# ground_station_DTMF.net
KiCad netlist of a schematic drawn in Altium Designer
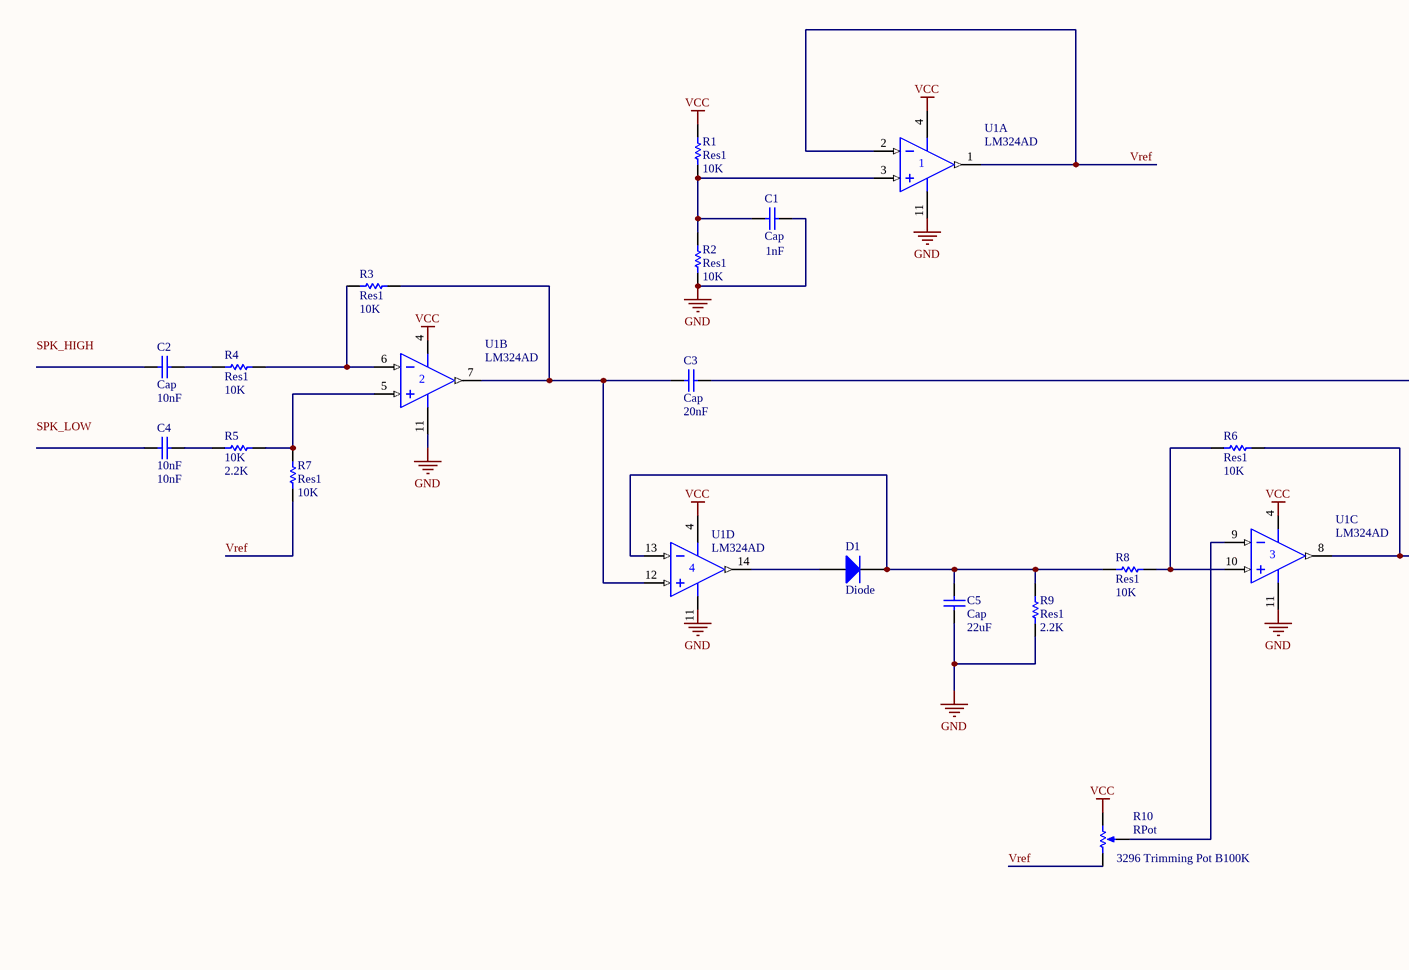
[diagram p0: ground station DTMF.SchDoc, left]
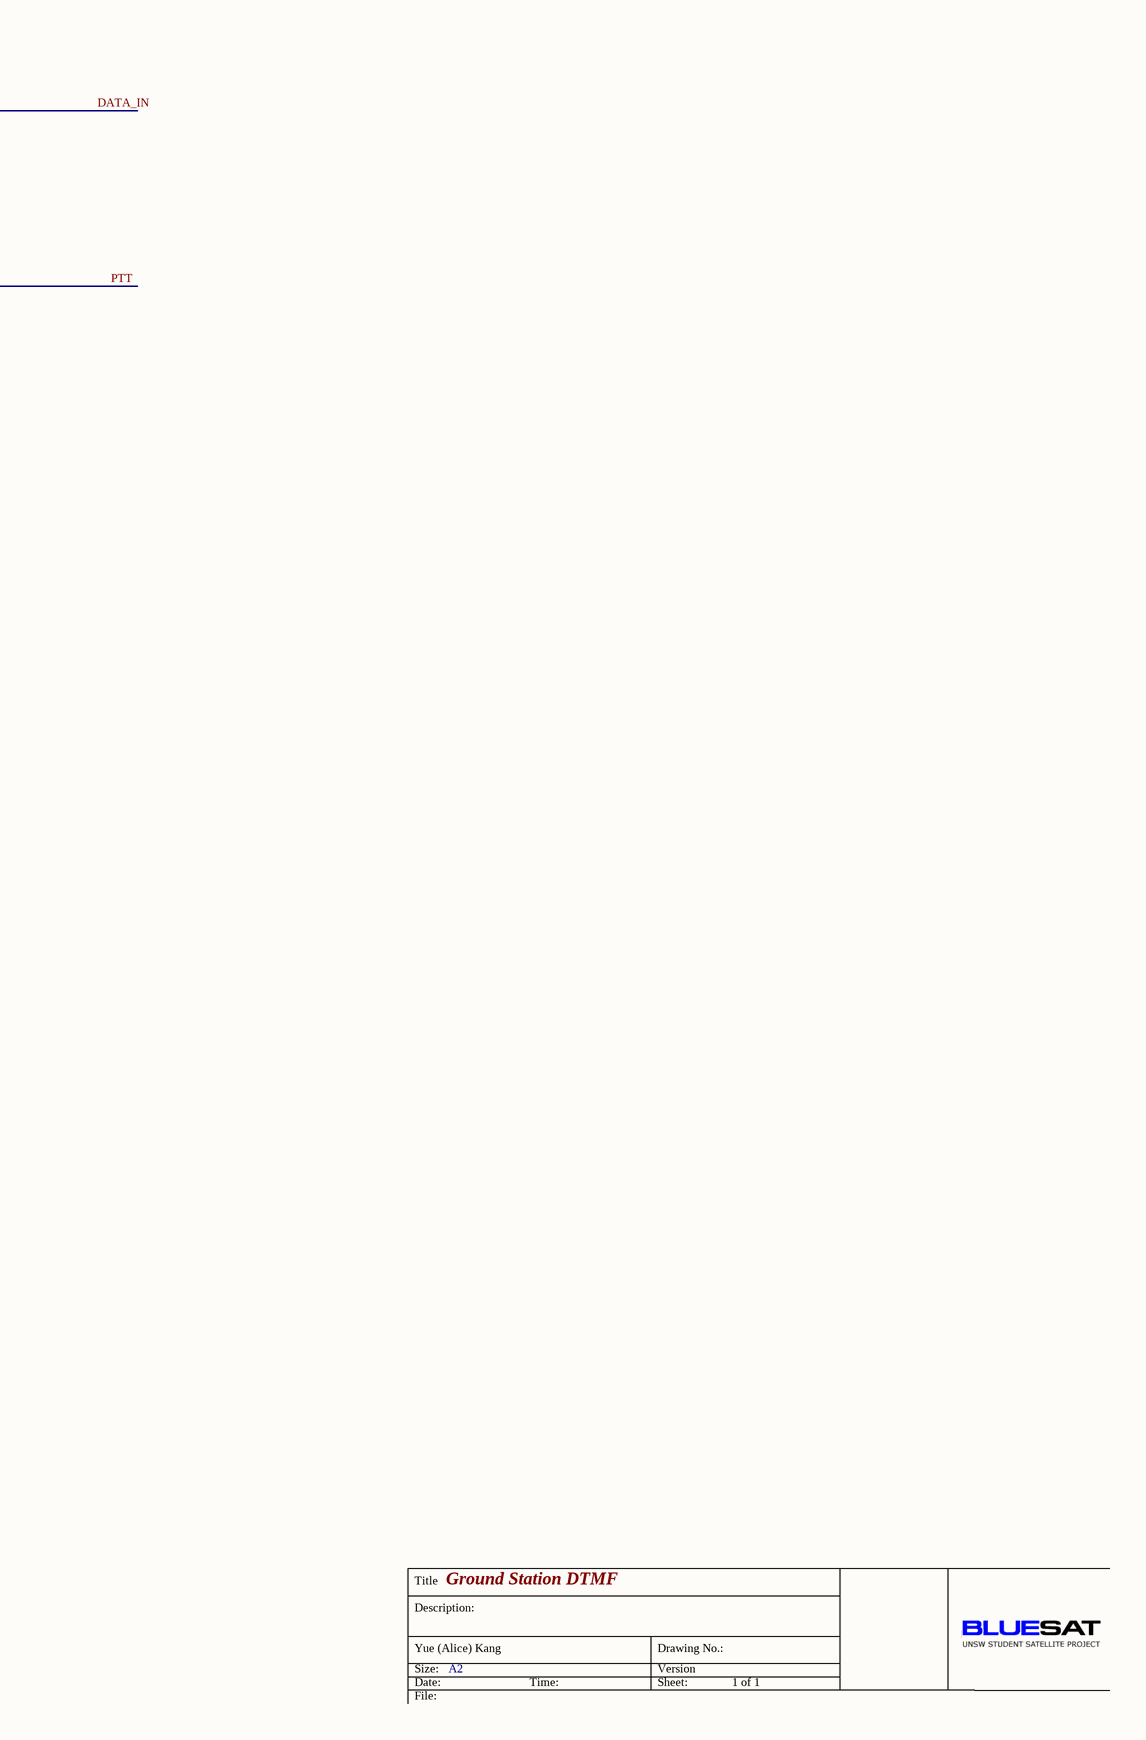
[diagram p1: ground station DTMF.SchDoc, right]

(export (version "E")
  (design (tool "Eeschema 10.0.6"))
  (components
    (comp (ref "C1")
      (value "Cap")
      (footprint "0805_RES")
      (description "Capacitor")
      (fields (field (name "ALTIUM_VALUE") "1nF") (field (name "PUBLISHER") "Altium Limited"))
      (libsource (lib "Miscellaneous Devices") (part "Cap"))
    )
    (comp (ref "C2")
      (value "Cap")
      (footprint "0805_RES")
      (description "Capacitor")
      (fields (field (name "ALTIUM_VALUE") "10nF") (field (name "PUBLISHER") "Altium Limited"))
      (libsource (lib "Miscellaneous Devices") (part "Cap"))
    )
    (comp (ref "C3")
      (value "Cap")
      (footprint "0805_RES")
      (description "Capacitor")
      (fields (field (name "ALTIUM_VALUE") "20nF") (field (name "PUBLISHER") "Altium Limited"))
      (libsource (lib "Miscellaneous Devices") (part "Cap"))
    )
    (comp (ref "C4")
      (value "10nF")
      (footprint "0805_RES")
      (description "Capacitor")
      (fields (field (name "ALTIUM_VALUE") "10nF") (field (name "PUBLISHER") "Altium Limited"))
      (libsource (lib "Miscellaneous Devices") (part "Cap"))
    )
    (comp (ref "C5")
      (value "Cap")
      (footprint "0805_RES")
      (description "Capacitor")
      (fields (field (name "ALTIUM_VALUE") "22uF") (field (name "PUBLISHER") "Altium Limited"))
      (libsource (lib "Miscellaneous Devices") (part "Cap"))
    )
    (comp (ref "D1")
      (value "Diode")
      (footprint "SMC")
      (description "Default Diode")
      (fields (field (name "PUBLISHER") "Altium Limited"))
      (libsource (lib "Miscellaneous Devices") (part "Diode"))
    )
    (comp (ref "R1")
      (value "Res1")
      (footprint "0805 RES CAP:0805_RES")
      (description "Resistor")
      (fields (field (name "ALTIUM_VALUE") "10K") (field (name "PUBLISHER") "Altium Limited"))
      (libsource (lib "Miscellaneous Devices") (part "Res1"))
    )
    (comp (ref "R2")
      (value "Res1")
      (footprint "0805_RES")
      (description "Resistor")
      (fields (field (name "ALTIUM_VALUE") "10K") (field (name "PUBLISHER") "Altium Limited"))
      (libsource (lib "Miscellaneous Devices") (part "Res1"))
    )
    (comp (ref "R3")
      (value "Res1")
      (footprint "0805_RES")
      (description "Resistor")
      (fields (field (name "ALTIUM_VALUE") "10K") (field (name "PUBLISHER") "Altium Limited"))
      (libsource (lib "Miscellaneous Devices") (part "Res1"))
    )
    (comp (ref "R4")
      (value "Res1")
      (footprint "0805 RES CAP:0805_RES")
      (description "Resistor")
      (fields (field (name "ALTIUM_VALUE") "10K") (field (name "PUBLISHER") "Altium Limited"))
      (libsource (lib "Miscellaneous Devices") (part "Res1"))
    )
    (comp (ref "R5")
      (value "10K")
      (footprint "0805 RES CAP:0805_RES")
      (description "Resistor")
      (fields (field (name "ALTIUM_VALUE") "2.2K") (field (name "PUBLISHER") "Altium Limited"))
      (libsource (lib "Miscellaneous Devices") (part "Res1"))
    )
    (comp (ref "R6")
      (value "Res1")
      (footprint "0805_RES")
      (description "Resistor")
      (fields (field (name "ALTIUM_VALUE") "10K") (field (name "PUBLISHER") "Altium Limited"))
      (libsource (lib "Miscellaneous Devices") (part "Res1"))
    )
    (comp (ref "R7")
      (value "Res1")
      (footprint "0805_RES")
      (description "Resistor")
      (fields (field (name "ALTIUM_VALUE") "10K") (field (name "PUBLISHER") "Altium Limited"))
      (libsource (lib "Miscellaneous Devices") (part "Res1"))
    )
    (comp (ref "R8")
      (value "Res1")
      (footprint "0805_RES")
      (description "Resistor")
      (fields (field (name "ALTIUM_VALUE") "10K") (field (name "PUBLISHER") "Altium Limited"))
      (libsource (lib "Miscellaneous Devices") (part "Res1"))
    )
    (comp (ref "R9")
      (value "Res1")
      (footprint "0805_RES")
      (description "Resistor")
      (fields (field (name "ALTIUM_VALUE") "2.2K") (field (name "PUBLISHER") "Altium Limited"))
      (libsource (lib "Miscellaneous Devices") (part "Res1"))
    )
    (comp (ref "R10")
      (value "RPot")
      (footprint "VR5")
      (description "Potentiometer")
      (fields
        (field (name "3296 SQUARE TRIMMING POT") "3296 Trimming Pot B100K")
        (field (name "PUBLISHER") "Altium Limited")
      )
      (libsource (lib "Miscellaneous Devices") (part "RPot"))
    )
    (comp (ref "U1")
      (value "LM324AD")
      (footprint "SOIC127P600X175-14N")
      (description "Quad Low-Power Operational Amplifier")
      (fields (field (name "PUBLISHER") "Altium Limited"))
      (libsource (lib "Motorola Amplifier Operational Amplifier") (part "LM324AD"))
    )
  )
  (nets
    (net (code "1") (name "/DATA_IN") (class "Default")
      (node (ref "C3") (pin "2") (pinfunction "2_2") (pintype "passive"))
    )
    (net (code "2") (name "/PTT") (class "Default")
      (node (ref "R6") (pin "2") (pinfunction "2_2") (pintype "passive"))
      (node (ref "U1") (pin "8") (pinfunction "OUT_8") (pintype "output"))
    )
    (net (code "5") (name "/Vref") (class "Default")
      (node (ref "R10") (pin "1") (pinfunction "TOP_1") (pintype "passive"))
      (node (ref "R7") (pin "1") (pinfunction "1_1") (pintype "passive"))
      (node (ref "U1") (pin "1") (pinfunction "OUT_1") (pintype "output"))
      (node (ref "U1") (pin "2") (pinfunction "IN-_2") (pintype "input"))
    )
    (net (code "6") (name "GND") (class "Default")
      (node (ref "C1") (pin "2") (pinfunction "2_2") (pintype "passive"))
      (node (ref "C5") (pin "1") (pinfunction "1_1") (pintype "passive"))
      (node (ref "R2") (pin "1") (pinfunction "1_1") (pintype "passive"))
      (node (ref "R9") (pin "1") (pinfunction "1_1") (pintype "passive"))
      (node (ref "U1") (pin "11") (pinfunction "V-_11") (pintype "power_in"))
    )
    (net (code "7") (name "Net-(C2-Pad2)") (class "Default")
      (node (ref "C2") (pin "2") (pinfunction "2_2") (pintype "passive"))
      (node (ref "R4") (pin "1") (pinfunction "1_1") (pintype "passive"))
    )
    (net (code "8") (name "Net-(C4-Pad2)") (class "Default")
      (node (ref "C4") (pin "2") (pinfunction "2_2") (pintype "passive"))
      (node (ref "R5") (pin "1") (pinfunction "1_1") (pintype "passive"))
    )
    (net (code "9") (name "Net-(D1-A)") (class "Default")
      (node (ref "D1") (pin "1") (pinfunction "A_1") (pintype "passive"))
      (node (ref "U1") (pin "14") (pinfunction "OUT_14") (pintype "output"))
    )
    (net (code "10") (name "Net-(D1-K)") (class "Default")
      (node (ref "C5") (pin "2") (pinfunction "2_2") (pintype "passive"))
      (node (ref "D1") (pin "2") (pinfunction "K_2") (pintype "passive"))
      (node (ref "R8") (pin "1") (pinfunction "1_1") (pintype "passive"))
      (node (ref "R9") (pin "2") (pinfunction "2_2") (pintype "passive"))
      (node (ref "U1") (pin "13") (pinfunction "IN-_13") (pintype "input"))
    )
    (net (code "11") (name "Net-(R10-TAP)") (class "Default")
      (node (ref "R10") (pin "3") (pinfunction "TAP_3") (pintype "passive"))
      (node (ref "U1") (pin "9") (pinfunction "IN-_9") (pintype "input"))
    )
    (net (code "12") (name "Net-(U1A-IN+)") (class "Default")
      (node (ref "C1") (pin "1") (pinfunction "1_1") (pintype "passive"))
      (node (ref "R1") (pin "1") (pinfunction "1_1") (pintype "passive"))
      (node (ref "R2") (pin "2") (pinfunction "2_2") (pintype "passive"))
      (node (ref "U1") (pin "3") (pinfunction "IN+_3") (pintype "input"))
    )
    (net (code "13") (name "Net-(U1B-IN+)") (class "Default")
      (node (ref "R5") (pin "2") (pinfunction "2_2") (pintype "passive"))
      (node (ref "R7") (pin "2") (pinfunction "2_2") (pintype "passive"))
      (node (ref "U1") (pin "5") (pinfunction "IN+_5") (pintype "input"))
    )
    (net (code "14") (name "Net-(U1B-IN-)") (class "Default")
      (node (ref "R3") (pin "1") (pinfunction "1_1") (pintype "passive"))
      (node (ref "R4") (pin "2") (pinfunction "2_2") (pintype "passive"))
      (node (ref "U1") (pin "6") (pinfunction "IN-_6") (pintype "input"))
    )
    (net (code "15") (name "Net-(U1B-OUT)") (class "Default")
      (node (ref "C3") (pin "1") (pinfunction "1_1") (pintype "passive"))
      (node (ref "R3") (pin "2") (pinfunction "2_2") (pintype "passive"))
      (node (ref "U1") (pin "12") (pinfunction "IN+_12") (pintype "input"))
      (node (ref "U1") (pin "7") (pinfunction "OUT_7") (pintype "output"))
    )
    (net (code "16") (name "Net-(U1C-IN+)") (class "Default")
      (node (ref "R6") (pin "1") (pinfunction "1_1") (pintype "passive"))
      (node (ref "R8") (pin "2") (pinfunction "2_2") (pintype "passive"))
      (node (ref "U1") (pin "10") (pinfunction "IN+_10") (pintype "input"))
    )
    (net (code "17") (name "VCC") (class "Default")
      (node (ref "R1") (pin "2") (pinfunction "2_2") (pintype "passive"))
      (node (ref "R10") (pin "2") (pinfunction "BOT_2") (pintype "passive"))
      (node (ref "U1") (pin "4") (pinfunction "V+_4") (pintype "power_in"))
    )
    (net (code "18") (name "unconnected-(C2-Pad1)") (class "Default")
      (node (ref "C2") (pin "1") (pinfunction "1_1") (pintype "passive"))
    )
    (net (code "19") (name "unconnected-(C4-Pad1)") (class "Default")
      (node (ref "C4") (pin "1") (pinfunction "1_1") (pintype "passive"))
    )
    (net (code "20") (name "unconnected-(U1B-V+-Pad4)") (class "Default")
      (node (ref "U1") (pin "4") (pinfunction "V+_4") (pintype "power_in"))
    )
    (net (code "21") (name "unconnected-(U1C-V+-Pad4)") (class "Default")
      (node (ref "U1") (pin "4") (pinfunction "V+_4") (pintype "power_in"))
    )
    (net (code "22") (name "unconnected-(U1D-V--Pad11)") (class "Default")
      (node (ref "U1") (pin "11") (pinfunction "V-_11") (pintype "power_in"))
    )
  )
)
